# SHARP_GP2AP03VT00F_V0_2_20200112.net
KiCad netlist of a schematic drawn in Altium Designer
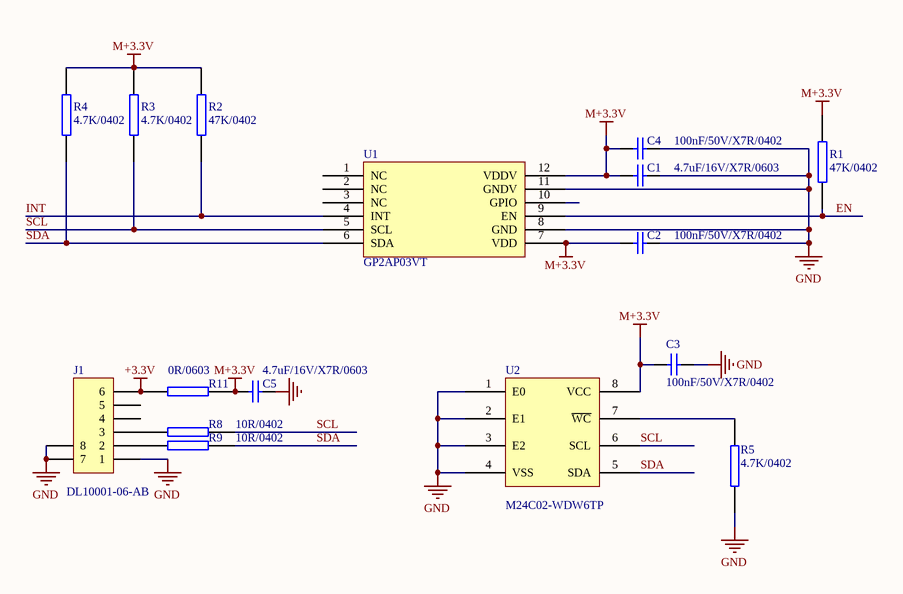
[diagram p0: SHARP_GP2AP03VT00F_V0.2_20200112.SchDoc]

(export (version "E")
  (design (tool "Eeschema 10.0.6"))
  (components
    (comp (ref "C1")
      (value "4.7uF/16V/X7R/0603")
      (footprint "CAP-CC0603")
      (description "CAP CER 4.7uF 16V 10% X7R 0603")
      (fields (field (name "Comment") "Cap"))
      (libsource (lib "Miscellaneous Devices") (part "Cap"))
    )
    (comp (ref "C2")
      (value "100nF/50V/X7R/0402")
      (footprint "CAP-CC0402")
      (description "CAP CER 100nF 50V 10% X7R 0402")
      (fields (field (name "Comment") "Cap"))
      (libsource (lib "Miscellaneous Devices") (part "Cap"))
    )
    (comp (ref "C3")
      (value "100nF/50V/X7R/0402")
      (footprint "CAP-CC0402")
      (description "CAP CER 100nF 50V 10% X7R 0402")
      (fields (field (name "Comment") "Cap"))
      (libsource (lib "Miscellaneous Devices") (part "Cap"))
    )
    (comp (ref "C4")
      (value "100nF/50V/X7R/0402")
      (footprint "CAP-CC0402")
      (description "CAP CER 100nF 50V 10% X7R 0402")
      (fields (field (name "Comment") "Cap"))
      (libsource (lib "Miscellaneous Devices") (part "Cap"))
    )
    (comp (ref "C5")
      (value "4.7uF/16V/X7R/0603")
      (footprint "CAP-CC0603")
      (description "CAP CER 4.7uF 16V 10% X7R 0603")
      (fields (field (name "Comment") "Cap"))
      (libsource (lib "Miscellaneous Devices") (part "Cap"))
    )
    (comp (ref "J1")
      (value "DL10001-06-AB")
      (footprint "A1001AWV-06")
      (description "SMT Header 6-Pin 1.0mm white VT")
      (fields (field (name "Comment") "CONNECT"))
      (libsource (lib "Schlib1") (part "CON6"))
    )
    (comp (ref "R1")
      (value "47K/0402")
      (footprint "RES-RC0402")
      (description "RES MF 47K 1/16W 5% 0402")
      (fields (field (name "Comment") "RES"))
      (libsource (lib "*") (part "RES2"))
    )
    (comp (ref "R2")
      (value "47K/0402")
      (footprint "RES-RC0402")
      (description "RES MF 47K 1/16W 5% 0402")
      (fields (field (name "Comment") "RES"))
      (libsource (lib "*") (part "RES2"))
    )
    (comp (ref "R3")
      (value "4.7K/0402")
      (footprint "RES-RC0402")
      (description "RES MF 4.7K 1/16W 5% 0402")
      (fields (field (name "Comment") "RES"))
      (libsource (lib "*") (part "RES2"))
    )
    (comp (ref "R4")
      (value "4.7K/0402")
      (footprint "RES-RC0402")
      (description "RES MF 4.7K 1/16W 5% 0402")
      (fields (field (name "Comment") "RES"))
      (libsource (lib "*") (part "RES2"))
    )
    (comp (ref "R5")
      (value "4.7K/0402")
      (footprint "RES-RC0402")
      (description "RES MF 4.7K 1/16W 5% 0402")
      (fields (field (name "Comment") "RES"))
      (libsource (lib "*") (part "RES2"))
    )
    (comp (ref "R8")
      (value "10R/0402")
      (footprint "RES-RC0402")
      (description "RES MF 10R 1/16W 5% 0402")
      (fields (field (name "Comment") "RES"))
      (libsource (lib "*") (part "RES2"))
    )
    (comp (ref "R9")
      (value "10R/0402")
      (footprint "RES-RC0402")
      (description "RES MF 10R 1/16W 5% 0402")
      (fields (field (name "Comment") "RES"))
      (libsource (lib "*") (part "RES2"))
    )
    (comp (ref "R11")
      (value "0R/0603")
      (footprint "RES-RC0603")
      (description "RES MF 10R 1/16W 5% 0402")
      (fields (field (name "Comment") "RES"))
      (libsource (lib "*") (part "RES2"))
    )
    (comp (ref "U1")
      (value "GP2AP03VT")
      (footprint "SHARP_GP2AP03VT00F")
      (fields (field (name "Comment") "IC"))
      (libsource (lib "Schlib1") (part "GP2AP03VT"))
    )
    (comp (ref "U2")
      (value "M24C02-WDW6TP")
      (footprint "TSSOP-8")
      (description "EEPROM,M24C02-WDW6TP,2K,TSSOP-8")
      (fields (field (name "Comment") "IC"))
      (libsource (lib "EEPROM") (part "Component_1"))
    )
  )
  (nets
    (net (code "1") (name "+3.3V") (class "Default")
      (node (ref "J1") (pin "6") (pinfunction "6_6") (pintype "passive"))
      (node (ref "R11") (pin "1") (pinfunction "1_1") (pintype "passive"))
    )
    (net (code "2") (name "/EN") (class "Default")
      (node (ref "R1") (pin "2") (pinfunction "2_2") (pintype "passive"))
      (node (ref "U1") (pin "9") (pinfunction "EN_9") (pintype "passive"))
    )
    (net (code "3") (name "/INT") (class "Default")
      (node (ref "R2") (pin "2") (pinfunction "2_2") (pintype "passive"))
      (node (ref "U1") (pin "4") (pinfunction "INT_4") (pintype "passive"))
    )
    (net (code "4") (name "/SCL") (class "Default")
      (node (ref "R3") (pin "2") (pinfunction "2_2") (pintype "passive"))
      (node (ref "R8") (pin "2") (pinfunction "2_2") (pintype "passive"))
      (node (ref "U1") (pin "5") (pinfunction "SCL_5") (pintype "passive"))
      (node (ref "U2") (pin "6") (pinfunction "SCL_6") (pintype "passive"))
    )
    (net (code "5") (name "/SDA") (class "Default")
      (node (ref "R4") (pin "2") (pinfunction "2_2") (pintype "passive"))
      (node (ref "R9") (pin "2") (pinfunction "2_2") (pintype "passive"))
      (node (ref "U1") (pin "6") (pinfunction "SDA_6") (pintype "passive"))
      (node (ref "U2") (pin "5") (pinfunction "SDA_5") (pintype "passive"))
    )
    (net (code "6") (name "GND") (class "Default")
      (node (ref "C1") (pin "2") (pinfunction "2_2") (pintype "passive"))
      (node (ref "C2") (pin "2") (pinfunction "2_2") (pintype "passive"))
      (node (ref "C3") (pin "2") (pinfunction "2_2") (pintype "passive"))
      (node (ref "C4") (pin "2") (pinfunction "2_2") (pintype "passive"))
      (node (ref "C5") (pin "2") (pinfunction "2_2") (pintype "passive"))
      (node (ref "J1") (pin "1") (pinfunction "1_1") (pintype "passive"))
      (node (ref "J1") (pin "7") (pinfunction "7_7") (pintype "power_in"))
      (node (ref "J1") (pin "8") (pinfunction "8_8") (pintype "power_in"))
      (node (ref "R5") (pin "2") (pinfunction "2_2") (pintype "passive"))
      (node (ref "U1") (pin "11") (pinfunction "GNDV_11") (pintype "passive"))
      (node (ref "U1") (pin "8") (pinfunction "GND_8") (pintype "passive"))
      (node (ref "U2") (pin "1") (pinfunction "E0_1") (pintype "passive"))
      (node (ref "U2") (pin "2") (pinfunction "E1_2") (pintype "passive"))
      (node (ref "U2") (pin "3") (pinfunction "E2_3") (pintype "passive"))
      (node (ref "U2") (pin "4") (pinfunction "VSS_4") (pintype "passive"))
    )
    (net (code "7") (name "M+3.3V") (class "Default")
      (node (ref "C1") (pin "1") (pinfunction "1_1") (pintype "passive"))
      (node (ref "C2") (pin "1") (pinfunction "1_1") (pintype "passive"))
      (node (ref "C3") (pin "1") (pinfunction "1_1") (pintype "passive"))
      (node (ref "C4") (pin "1") (pinfunction "1_1") (pintype "passive"))
      (node (ref "C5") (pin "1") (pinfunction "1_1") (pintype "passive"))
      (node (ref "R1") (pin "1") (pinfunction "1_1") (pintype "passive"))
      (node (ref "R11") (pin "2") (pinfunction "2_2") (pintype "passive"))
      (node (ref "R2") (pin "1") (pinfunction "1_1") (pintype "passive"))
      (node (ref "R3") (pin "1") (pinfunction "1_1") (pintype "passive"))
      (node (ref "R4") (pin "1") (pinfunction "1_1") (pintype "passive"))
      (node (ref "U1") (pin "12") (pinfunction "VDDV_12") (pintype "passive"))
      (node (ref "U1") (pin "7") (pinfunction "VDD_7") (pintype "passive"))
      (node (ref "U2") (pin "8") (pinfunction "VCC_8") (pintype "passive"))
    )
    (net (code "8") (name "Net-(J1-Pad2)") (class "Default")
      (node (ref "J1") (pin "2") (pinfunction "2_2") (pintype "passive"))
      (node (ref "R9") (pin "1") (pinfunction "1_1") (pintype "passive"))
    )
    (net (code "9") (name "Net-(J1-Pad3)") (class "Default")
      (node (ref "J1") (pin "3") (pinfunction "3_3") (pintype "passive"))
      (node (ref "R8") (pin "1") (pinfunction "1_1") (pintype "passive"))
    )
    (net (code "10") (name "Net-(U2-~{WC})") (class "Default")
      (node (ref "R5") (pin "1") (pinfunction "1_1") (pintype "passive"))
      (node (ref "U2") (pin "7") (pinfunction "~{WC}_7") (pintype "passive"))
    )
    (net (code "11") (name "unconnected-(J1-Pad4)") (class "Default")
      (node (ref "J1") (pin "4") (pinfunction "4_4") (pintype "passive"))
    )
    (net (code "12") (name "unconnected-(J1-Pad5)") (class "Default")
      (node (ref "J1") (pin "5") (pinfunction "5_5") (pintype "passive"))
    )
    (net (code "13") (name "unconnected-(U1-GPIO-Pad10)") (class "Default")
      (node (ref "U1") (pin "10") (pinfunction "GPIO_10") (pintype "passive"))
    )
    (net (code "14") (name "unconnected-(U1-NC-Pad1)") (class "Default")
      (node (ref "U1") (pin "1") (pinfunction "NC_1") (pintype "passive"))
    )
    (net (code "15") (name "unconnected-(U1-NC-Pad2)") (class "Default")
      (node (ref "U1") (pin "2") (pinfunction "NC_2") (pintype "passive"))
    )
    (net (code "16") (name "unconnected-(U1-NC-Pad3)") (class "Default")
      (node (ref "U1") (pin "3") (pinfunction "NC_3") (pintype "passive"))
    )
  )
)
